# GNDing.net
KiCad netlist of a schematic drawn in Altium Designer
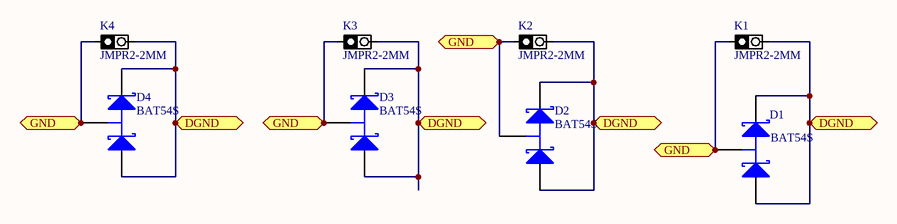
[diagram p0: GNDing.SchDoc]

(export (version "E")
  (design (tool "Eeschema 10.0.6"))
  (components
    (comp (ref "D1")
      (value "BAT54S")
      (footprint "SOT23_N")
      (description "Schottky Barrier Double Diode")
      (fields (field (name "PUBLISHER") "Altium Limited"))
      (libsource (lib "Philips Discrete Diode - Schottky") (part "BAT54S"))
    )
    (comp (ref "D2")
      (value "BAT54S")
      (footprint "SOT23_N")
      (description "Schottky Barrier Double Diode")
      (fields (field (name "PUBLISHER") "Altium Limited"))
      (libsource (lib "Philips Discrete Diode - Schottky") (part "BAT54S"))
    )
    (comp (ref "D3")
      (value "BAT54S")
      (footprint "SOT23_N")
      (description "Schottky Barrier Double Diode")
      (fields (field (name "PUBLISHER") "Altium Limited"))
      (libsource (lib "Philips Discrete Diode - Schottky") (part "BAT54S"))
    )
    (comp (ref "D4")
      (value "BAT54S")
      (footprint "SOT23_N")
      (description "Schottky Barrier Double Diode")
      (fields (field (name "PUBLISHER") "Altium Limited"))
      (libsource (lib "Philips Discrete Diode - Schottky") (part "BAT54S"))
    )
    (comp (ref "K1")
      (value "JMPR2-2MM")
      (footprint "JMPR2-2MM")
      (description "JMPR2 2MM OPEN BY DEFAULT")
      (fields
        (field (name "MANUFACTURER") "Sullins Connector Solutions")
        (field (name "MANUFACTURER PART NUMBER") "PBC36SAAN")
      )
      (libsource (lib "vh_altium_library") (part "JMPR2-2MM"))
    )
    (comp (ref "K2")
      (value "JMPR2-2MM")
      (footprint "JMPR2-2MM")
      (description "JMPR2 2MM OPEN BY DEFAULT")
      (fields
        (field (name "MANUFACTURER") "Sullins Connector Solutions")
        (field (name "MANUFACTURER PART NUMBER") "PBC36SAAN")
      )
      (libsource (lib "vh_altium_library") (part "JMPR2-2MM"))
    )
    (comp (ref "K3")
      (value "JMPR2-2MM")
      (footprint "JMPR2-2MM")
      (description "JMPR2 2MM OPEN BY DEFAULT")
      (fields
        (field (name "MANUFACTURER") "Sullins Connector Solutions")
        (field (name "MANUFACTURER PART NUMBER") "PBC36SAAN")
      )
      (libsource (lib "vh_altium_library") (part "JMPR2-2MM"))
    )
    (comp (ref "K4")
      (value "JMPR2-2MM")
      (footprint "JMPR2-2MM")
      (description "JMPR2 2MM OPEN BY DEFAULT")
      (fields
        (field (name "MANUFACTURER") "Sullins Connector Solutions")
        (field (name "MANUFACTURER PART NUMBER") "PBC36SAAN")
      )
      (libsource (lib "vh_altium_library") (part "JMPR2-2MM"))
    )
  )
  (nets
    (net (code "1") (name "/DGND") (class "Default")
      (node (ref "D1") (pin "1") (pinfunction "A_1") (pintype "passive"))
      (node (ref "D1") (pin "2") (pinfunction "K_2") (pintype "passive"))
      (node (ref "D2") (pin "1") (pinfunction "A_1") (pintype "passive"))
      (node (ref "D2") (pin "2") (pinfunction "K_2") (pintype "passive"))
      (node (ref "D3") (pin "1") (pinfunction "A_1") (pintype "passive"))
      (node (ref "D3") (pin "2") (pinfunction "K_2") (pintype "passive"))
      (node (ref "D4") (pin "1") (pinfunction "A_1") (pintype "passive"))
      (node (ref "D4") (pin "2") (pinfunction "K_2") (pintype "passive"))
      (node (ref "K1") (pin "2") (pintype "passive"))
      (node (ref "K2") (pin "2") (pintype "passive"))
      (node (ref "K3") (pin "2") (pintype "passive"))
      (node (ref "K4") (pin "2") (pintype "passive"))
    )
    (net (code "2") (name "/GND") (class "Default")
      (node (ref "D1") (pin "3") (pinfunction "C_3") (pintype "passive"))
      (node (ref "D2") (pin "3") (pinfunction "C_3") (pintype "passive"))
      (node (ref "D3") (pin "3") (pinfunction "C_3") (pintype "passive"))
      (node (ref "D4") (pin "3") (pinfunction "C_3") (pintype "passive"))
      (node (ref "K1") (pin "1") (pintype "passive"))
      (node (ref "K2") (pin "1") (pintype "passive"))
      (node (ref "K3") (pin "1") (pintype "passive"))
      (node (ref "K4") (pin "1") (pintype "passive"))
    )
  )
)
